# motordDrive_BreakOut.net
KiCad netlist of a schematic drawn in EAGLE
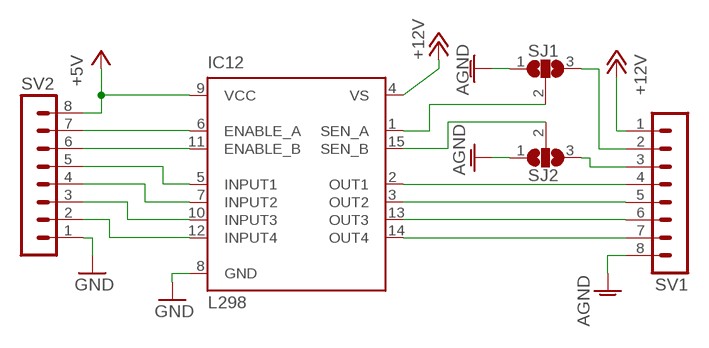
[diagram p0: schematic, sheet 1]

(export (version "E")
  (design (tool "Eeschema 10.0.6"))
  (components
    (comp (ref "IC12")
      (value "L298")
      (footprint "eagle-import:MULTIWATT-15")
      (fields (field (name "MPN") "L298N"))
      (libsource (lib "eagle-import") (part "L298"))
    )
    (comp (ref "SJ1")
      (value "SJ2WW")
      (footprint "eagle-import:SJ_2W")
      (libsource (lib "eagle-import") (part "SJ2WW"))
    )
    (comp (ref "SJ2")
      (value "SJ2WW")
      (footprint "eagle-import:SJ_2W")
      (libsource (lib "eagle-import") (part "SJ2WW"))
    )
    (comp (ref "SV1")
      (value "MA08-1")
      (footprint "eagle-import:MA08-1")
      (libsource (lib "eagle-import") (part "MA08-1"))
    )
    (comp (ref "SV2")
      (value "MA08-1")
      (footprint "eagle-import:MA08-1")
      (libsource (lib "eagle-import") (part "MA08-1"))
    )
  )
  (nets
    (net (code "1") (name "+5V") (class "Default")
      (node (ref "IC12") (pin "9") (pinfunction "VCC_9") (pintype "power_in"))
      (node (ref "SV2") (pin "8") (pinfunction "8_8") (pintype "passive"))
    )
    (net (code "2") (name "+12V") (class "Default")
      (node (ref "IC12") (pin "4") (pinfunction "VS_4") (pintype "power_in"))
      (node (ref "SV1") (pin "1") (pinfunction "1_1") (pintype "passive"))
    )
    (net (code "3") (name "AGND") (class "Default")
      (node (ref "SJ1") (pin "1") (pinfunction "1_1") (pintype "passive"))
      (node (ref "SJ2") (pin "1") (pinfunction "1_1") (pintype "passive"))
      (node (ref "SV1") (pin "8") (pinfunction "8_8") (pintype "passive"))
    )
    (net (code "4") (name "GND") (class "Default")
      (node (ref "IC12") (pin "8") (pinfunction "GND_8") (pintype "power_in"))
      (node (ref "SV2") (pin "1") (pinfunction "1_1") (pintype "passive"))
    )
    (net (code "5") (name "Net-(IC12-ENABLE_A)") (class "Default")
      (node (ref "IC12") (pin "6") (pinfunction "ENABLE_A_6") (pintype "input"))
      (node (ref "SV2") (pin "7") (pinfunction "7_7") (pintype "passive"))
    )
    (net (code "6") (name "Net-(IC12-ENABLE_B)") (class "Default")
      (node (ref "IC12") (pin "11") (pinfunction "ENABLE_B_11") (pintype "input"))
      (node (ref "SV2") (pin "6") (pinfunction "6_6") (pintype "passive"))
    )
    (net (code "7") (name "Net-(IC12-INPUT1)") (class "Default")
      (node (ref "IC12") (pin "5") (pinfunction "INPUT1_5") (pintype "input"))
      (node (ref "SV2") (pin "5") (pinfunction "5_5") (pintype "passive"))
    )
    (net (code "8") (name "Net-(IC12-INPUT2)") (class "Default")
      (node (ref "IC12") (pin "7") (pinfunction "INPUT2_7") (pintype "input"))
      (node (ref "SV2") (pin "4") (pinfunction "4_4") (pintype "passive"))
    )
    (net (code "9") (name "Net-(IC12-INPUT3)") (class "Default")
      (node (ref "IC12") (pin "10") (pinfunction "INPUT3_10") (pintype "input"))
      (node (ref "SV2") (pin "3") (pinfunction "3_3") (pintype "passive"))
    )
    (net (code "10") (name "Net-(IC12-INPUT4)") (class "Default")
      (node (ref "IC12") (pin "12") (pinfunction "INPUT4_12") (pintype "input"))
      (node (ref "SV2") (pin "2") (pinfunction "2_2") (pintype "passive"))
    )
    (net (code "11") (name "Net-(IC12-OUT1)") (class "Default")
      (node (ref "IC12") (pin "2") (pinfunction "OUT1_2") (pintype "output"))
      (node (ref "SV1") (pin "4") (pinfunction "4_4") (pintype "passive"))
    )
    (net (code "12") (name "Net-(IC12-OUT2)") (class "Default")
      (node (ref "IC12") (pin "3") (pinfunction "OUT2_3") (pintype "output"))
      (node (ref "SV1") (pin "5") (pinfunction "5_5") (pintype "passive"))
    )
    (net (code "13") (name "Net-(IC12-OUT3)") (class "Default")
      (node (ref "IC12") (pin "13") (pinfunction "OUT3_13") (pintype "output"))
      (node (ref "SV1") (pin "6") (pinfunction "6_6") (pintype "passive"))
    )
    (net (code "14") (name "Net-(IC12-OUT4)") (class "Default")
      (node (ref "IC12") (pin "14") (pinfunction "OUT4_14") (pintype "output"))
      (node (ref "SV1") (pin "7") (pinfunction "7_7") (pintype "passive"))
    )
    (net (code "15") (name "Net-(IC12-SEN_A)") (class "Default")
      (node (ref "IC12") (pin "1") (pinfunction "SEN_A_1") (pintype "input"))
      (node (ref "SJ1") (pin "2") (pinfunction "2_2") (pintype "passive"))
    )
    (net (code "16") (name "Net-(IC12-SEN_B)") (class "Default")
      (node (ref "IC12") (pin "15") (pinfunction "SEN_B_15") (pintype "input"))
      (node (ref "SJ2") (pin "2") (pinfunction "2_2") (pintype "passive"))
    )
    (net (code "17") (name "Net-(SJ1-Pad3)") (class "Default")
      (node (ref "SJ1") (pin "3") (pinfunction "3_3") (pintype "passive"))
      (node (ref "SV1") (pin "2") (pinfunction "2_2") (pintype "passive"))
    )
    (net (code "18") (name "Net-(SJ2-Pad3)") (class "Default")
      (node (ref "SJ2") (pin "3") (pinfunction "3_3") (pintype "passive"))
      (node (ref "SV1") (pin "3") (pinfunction "3_3") (pintype "passive"))
    )
  )
)
